# Layer_4.net
KiCad netlist of a schematic drawn in EAGLE
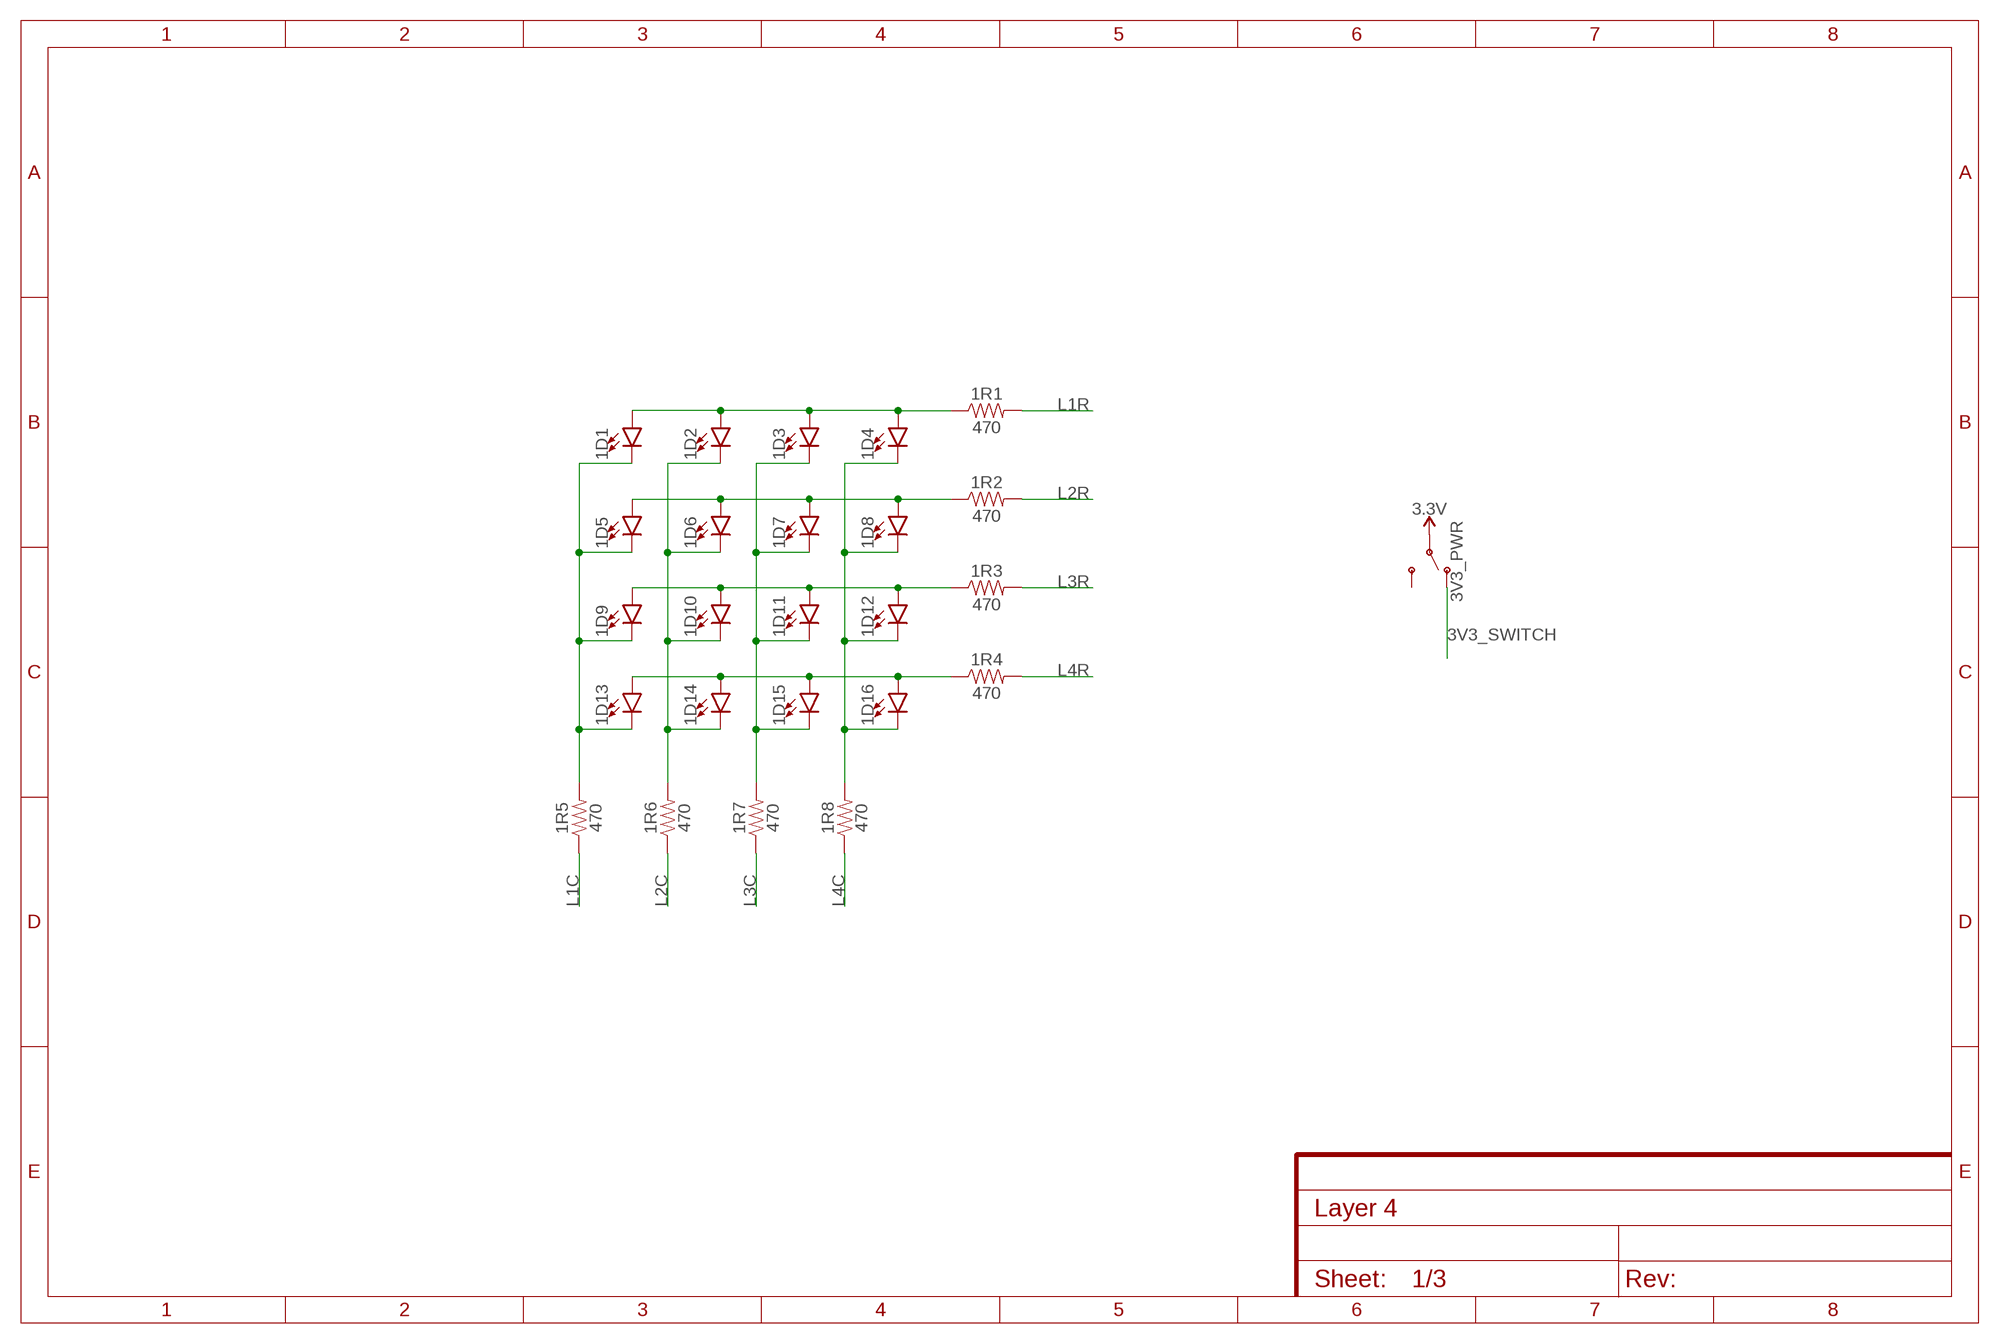
[diagram p0: schematic, sheet 1]
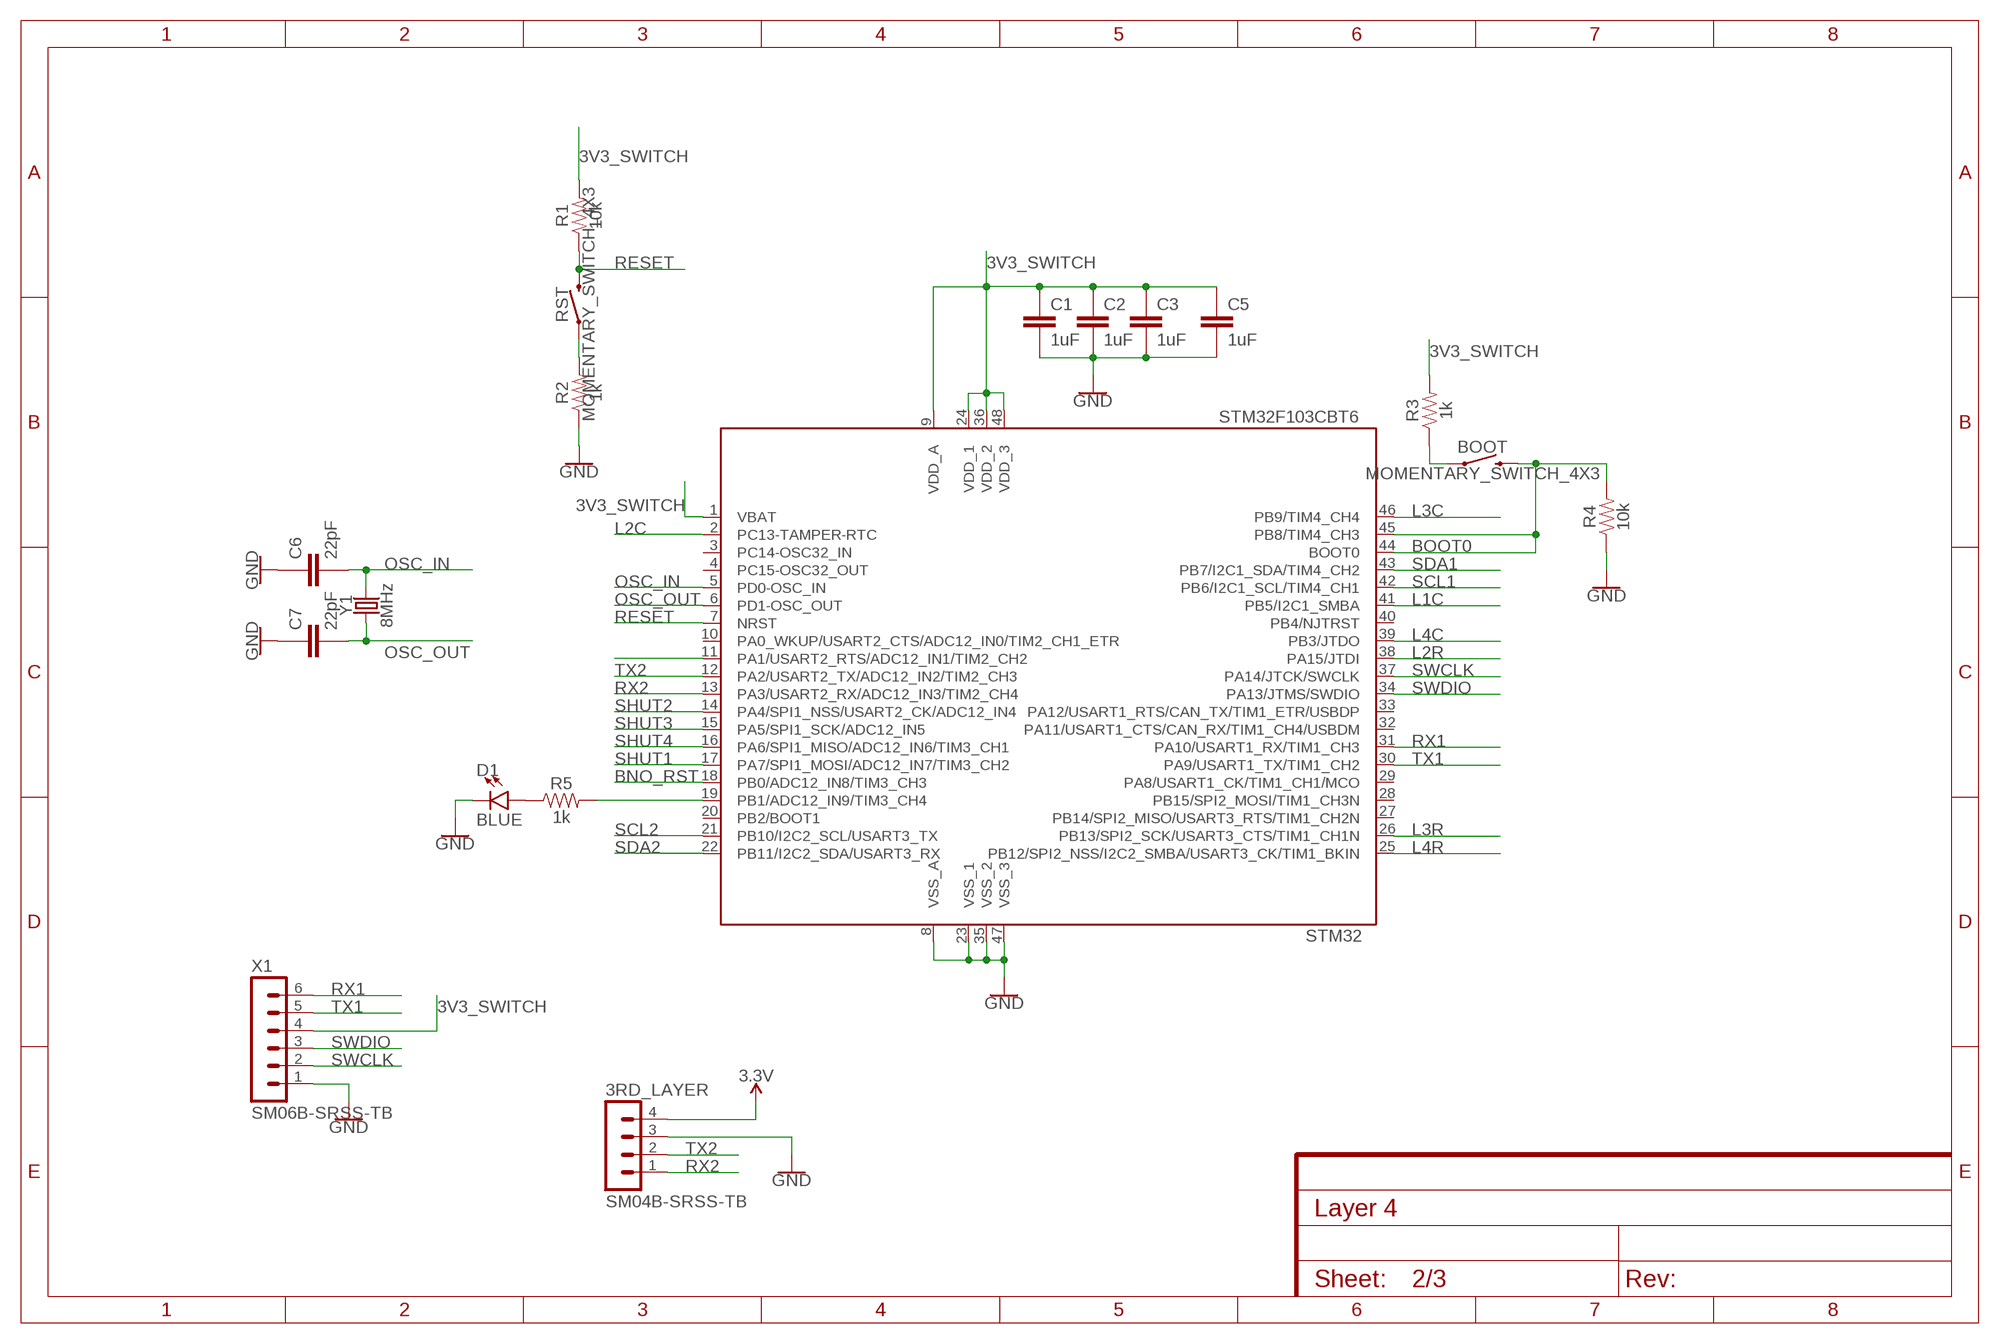
[diagram p1: schematic, sheet 2]
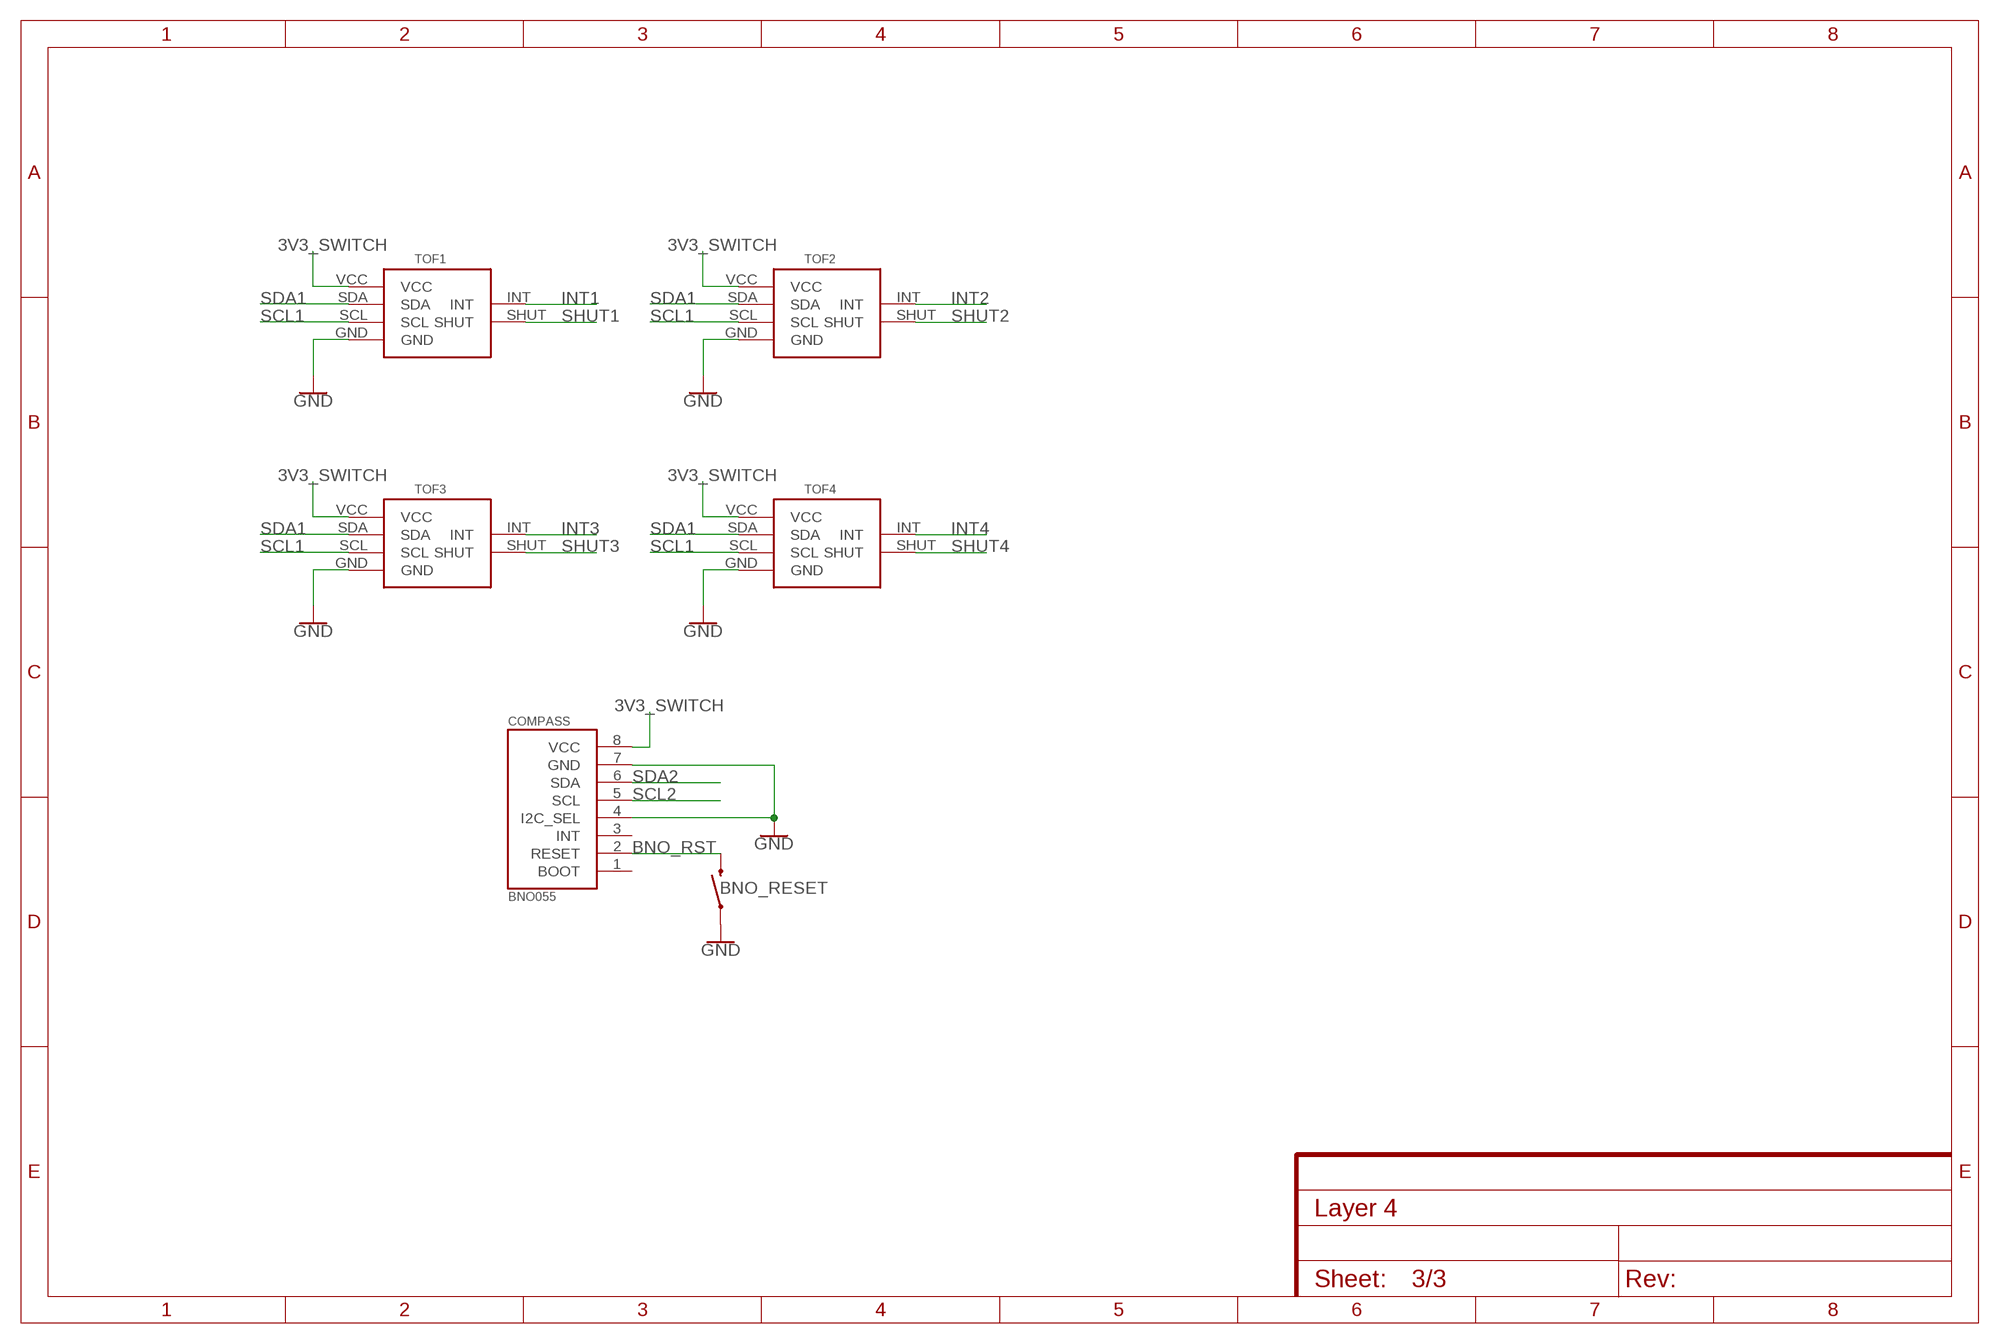
[diagram p2: schematic, sheet 3]

(export (version "E")
  (design (tool "Eeschema 10.0.6"))
  (components
    (comp (ref "1D1")
      (value "LED0603")
      (footprint "eagle-import:LED-0603")
      (libsource (lib "eagle-import") (part "LED0603"))
    )
    (comp (ref "1D2")
      (value "LED0603")
      (footprint "eagle-import:LED-0603")
      (libsource (lib "eagle-import") (part "LED0603"))
    )
    (comp (ref "1D3")
      (value "LED0603")
      (footprint "eagle-import:LED-0603")
      (libsource (lib "eagle-import") (part "LED0603"))
    )
    (comp (ref "1D4")
      (value "LED0603")
      (footprint "eagle-import:LED-0603")
      (libsource (lib "eagle-import") (part "LED0603"))
    )
    (comp (ref "1D5")
      (value "LED0603")
      (footprint "eagle-import:LED-0603")
      (libsource (lib "eagle-import") (part "LED0603"))
    )
    (comp (ref "1D6")
      (value "LED0603")
      (footprint "eagle-import:LED-0603")
      (libsource (lib "eagle-import") (part "LED0603"))
    )
    (comp (ref "1D7")
      (value "LED0603")
      (footprint "eagle-import:LED-0603")
      (libsource (lib "eagle-import") (part "LED0603"))
    )
    (comp (ref "1D8")
      (value "LED0603")
      (footprint "eagle-import:LED-0603")
      (libsource (lib "eagle-import") (part "LED0603"))
    )
    (comp (ref "1D9")
      (value "LED0603")
      (footprint "eagle-import:LED-0603")
      (libsource (lib "eagle-import") (part "LED0603"))
    )
    (comp (ref "1D10")
      (value "LED0603")
      (footprint "eagle-import:LED-0603")
      (libsource (lib "eagle-import") (part "LED0603"))
    )
    (comp (ref "1D11")
      (value "LED0603")
      (footprint "eagle-import:LED-0603")
      (libsource (lib "eagle-import") (part "LED0603"))
    )
    (comp (ref "1D12")
      (value "LED0603")
      (footprint "eagle-import:LED-0603")
      (libsource (lib "eagle-import") (part "LED0603"))
    )
    (comp (ref "1D13")
      (value "LED0603")
      (footprint "eagle-import:LED-0603")
      (libsource (lib "eagle-import") (part "LED0603"))
    )
    (comp (ref "1D14")
      (value "LED0603")
      (footprint "eagle-import:LED-0603")
      (libsource (lib "eagle-import") (part "LED0603"))
    )
    (comp (ref "1D15")
      (value "LED0603")
      (footprint "eagle-import:LED-0603")
      (libsource (lib "eagle-import") (part "LED0603"))
    )
    (comp (ref "1D16")
      (value "LED0603")
      (footprint "eagle-import:LED-0603")
      (libsource (lib "eagle-import") (part "LED0603"))
    )
    (comp (ref "1R1")
      (value "470")
      (footprint "eagle-import:R0603")
      (libsource (lib "eagle-import") (part "RESISTOR0603"))
    )
    (comp (ref "1R2")
      (value "470")
      (footprint "eagle-import:R0603")
      (libsource (lib "eagle-import") (part "RESISTOR0603"))
    )
    (comp (ref "1R3")
      (value "470")
      (footprint "eagle-import:R0603")
      (libsource (lib "eagle-import") (part "RESISTOR0603"))
    )
    (comp (ref "1R4")
      (value "470")
      (footprint "eagle-import:R0603")
      (libsource (lib "eagle-import") (part "RESISTOR0603"))
    )
    (comp (ref "1R5")
      (value "470")
      (footprint "eagle-import:R0603")
      (libsource (lib "eagle-import") (part "RESISTOR0603"))
    )
    (comp (ref "1R6")
      (value "470")
      (footprint "eagle-import:R0603")
      (libsource (lib "eagle-import") (part "RESISTOR0603"))
    )
    (comp (ref "1R7")
      (value "470")
      (footprint "eagle-import:R0603")
      (libsource (lib "eagle-import") (part "RESISTOR0603"))
    )
    (comp (ref "1R8")
      (value "470")
      (footprint "eagle-import:R0603")
      (libsource (lib "eagle-import") (part "RESISTOR0603"))
    )
    (comp (ref "3V3_PWR")
      (value "SWITCH-SPDT-PTH-11.6X4.0MM-LOCK")
      (footprint "eagle-import:SWITCH_SPDT_PTH_11.6X4.0MM_LOCK")
      (libsource (lib "eagle-import") (part "SWITCH-SPDT-PTH-11.6X4.0MM-LOCK"))
    )
    (comp (ref "3RD_LAYER")
      (value "SM04B-SRSS-TB")
      (footprint "eagle-import:SM04B-SRSS-TB")
      (libsource (lib "eagle-import") (part "SM04B-SRSS-TB"))
    )
    (comp (ref "BOOT")
      (value "MOMENTARY_SWITCH_4X3")
      (footprint "eagle-import:MOMENTARY_SWITCH_4X3")
      (libsource (lib "eagle-import") (part "MOMENTARY_SWITCH_4X3"))
    )
    (comp (ref "C1")
      (value "1uF")
      (footprint "eagle-import:C0603")
      (libsource (lib "eagle-import") (part "CAPACITOR0603"))
    )
    (comp (ref "C2")
      (value "1uF")
      (footprint "eagle-import:C0603")
      (libsource (lib "eagle-import") (part "CAPACITOR0603"))
    )
    (comp (ref "C3")
      (value "1uF")
      (footprint "eagle-import:C0603")
      (libsource (lib "eagle-import") (part "CAPACITOR0603"))
    )
    (comp (ref "C5")
      (value "1uF")
      (footprint "eagle-import:C0603")
      (libsource (lib "eagle-import") (part "CAPACITOR0603"))
    )
    (comp (ref "C6")
      (value "22pF")
      (footprint "eagle-import:C0603")
      (libsource (lib "eagle-import") (part "CAPACITOR0603"))
    )
    (comp (ref "C7")
      (value "22pF")
      (footprint "eagle-import:C0603")
      (libsource (lib "eagle-import") (part "CAPACITOR0603"))
    )
    (comp (ref "D1")
      (value "BLUE")
      (footprint "eagle-import:LED-0603")
      (libsource (lib "eagle-import") (part "LED0603"))
    )
    (comp (ref "R1")
      (value "10k")
      (footprint "eagle-import:R0603")
      (libsource (lib "eagle-import") (part "RESISTOR0603"))
    )
    (comp (ref "R2")
      (value "1k")
      (footprint "eagle-import:R0603")
      (libsource (lib "eagle-import") (part "RESISTOR0603"))
    )
    (comp (ref "R3")
      (value "1k")
      (footprint "eagle-import:R0603")
      (libsource (lib "eagle-import") (part "RESISTOR0603"))
    )
    (comp (ref "R4")
      (value "10k")
      (footprint "eagle-import:R0603")
      (libsource (lib "eagle-import") (part "RESISTOR0603"))
    )
    (comp (ref "R5")
      (value "1k")
      (footprint "eagle-import:R0603")
      (libsource (lib "eagle-import") (part "RESISTOR0603"))
    )
    (comp (ref "RST")
      (value "MOMENTARY_SWITCH_4X3")
      (footprint "eagle-import:MOMENTARY_SWITCH_4X3")
      (libsource (lib "eagle-import") (part "MOMENTARY_SWITCH_4X3"))
    )
    (comp (ref "STM32")
      (value "STM32F103CBT6")
      (footprint "eagle-import:LQFP48")
      (libsource (lib "eagle-import") (part "STM32F103CBT6"))
    )
    (comp (ref "X1")
      (value "SM06B-SRSS-TB")
      (footprint "eagle-import:SM06B-SRSS-TB")
      (libsource (lib "eagle-import") (part "SM06B-SRSS-TB"))
    )
    (comp (ref "Y1")
      (value "8MHz")
      (footprint "eagle-import:CRYSTAL-SMD-5X3.2-2PAD")
      (libsource (lib "eagle-import") (part "CRYSTALSMD-5X3.2-2PAD"))
    )
    (comp (ref "BNO_RESET")
      (value "MOMENTARY_SWITCH_4X3")
      (footprint "eagle-import:MOMENTARY_SWITCH_4X3")
      (libsource (lib "eagle-import") (part "MOMENTARY_SWITCH_4X3"))
    )
    (comp (ref "COMPASS")
      (value "BNO055")
      (footprint "eagle-import:BNO055")
      (libsource (lib "eagle-import") (part "BNO055"))
    )
    (comp (ref "TOF1")
      (value "VL53L1X")
      (footprint "eagle-import:VL53L1X_SLANTEDPINS")
      (libsource (lib "eagle-import") (part "VL53L1X"))
    )
    (comp (ref "TOF2")
      (value "VL53L1X")
      (footprint "eagle-import:VL53L1X_SLANTEDPINS")
      (libsource (lib "eagle-import") (part "VL53L1X"))
    )
    (comp (ref "TOF3")
      (value "VL53L1X")
      (footprint "eagle-import:VL53L1X_SLANTEDPINS")
      (libsource (lib "eagle-import") (part "VL53L1X"))
    )
    (comp (ref "TOF4")
      (value "VL53L1X")
      (footprint "eagle-import:VL53L1X_SLANTEDPINS")
      (libsource (lib "eagle-import") (part "VL53L1X"))
    )
  )
  (nets
    (net (code "1") (name "3.3V") (class "Default")
      (node (ref "3RD_LAYER") (pin "4") (pinfunction "4_4") (pintype "passive"))
      (node (ref "3V3_PWR") (pin "2") (pinfunction "P_2") (pintype "passive"))
    )
    (net (code "2") (name "3V3_SWITCH") (class "Default")
      (node (ref "3V3_PWR") (pin "1") (pinfunction "O_1") (pintype "passive"))
      (node (ref "C1") (pin "1") (pinfunction "1_1") (pintype "passive"))
      (node (ref "C2") (pin "1") (pinfunction "1_1") (pintype "passive"))
      (node (ref "C3") (pin "1") (pinfunction "1_1") (pintype "passive"))
      (node (ref "C5") (pin "2") (pinfunction "2_2") (pintype "passive"))
      (node (ref "COMPASS") (pin "8") (pinfunction "VCC_8") (pintype "bidirectional"))
      (node (ref "R1") (pin "2") (pinfunction "2_2") (pintype "passive"))
      (node (ref "R3") (pin "2") (pinfunction "2_2") (pintype "passive"))
      (node (ref "STM32") (pin "1") (pinfunction "VBAT_1") (pintype "power_in"))
      (node (ref "STM32") (pin "24") (pinfunction "VDD_1_24") (pintype "power_in"))
      (node (ref "STM32") (pin "36") (pinfunction "VDD_2_36") (pintype "power_in"))
      (node (ref "STM32") (pin "48") (pinfunction "VDD_3_48") (pintype "power_in"))
      (node (ref "STM32") (pin "9") (pinfunction "VDD_A_9") (pintype "power_in"))
      (node (ref "TOF1") (pin "VCC") (pinfunction "VCC_VCC") (pintype "power_in"))
      (node (ref "TOF2") (pin "VCC") (pinfunction "VCC_VCC") (pintype "power_in"))
      (node (ref "TOF3") (pin "VCC") (pinfunction "VCC_VCC") (pintype "power_in"))
      (node (ref "TOF4") (pin "VCC") (pinfunction "VCC_VCC") (pintype "power_in"))
      (node (ref "X1") (pin "4") (pinfunction "4_4") (pintype "passive"))
    )
    (net (code "3") (name "BNO_RST") (class "Default")
      (node (ref "BNO_RESET") (pin "P$2") (pinfunction "2_P$2") (pintype "passive"))
      (node (ref "COMPASS") (pin "2") (pinfunction "RESET_2") (pintype "bidirectional"))
      (node (ref "STM32") (pin "18") (pinfunction "PB0/ADC12_IN8/TIM3_CH3_18") (pintype "bidirectional"))
    )
    (net (code "4") (name "BOOT0") (class "Default")
      (node (ref "BOOT") (pin "P$2") (pinfunction "2_P$2") (pintype "passive"))
      (node (ref "R4") (pin "2") (pinfunction "2_2") (pintype "passive"))
      (node (ref "STM32") (pin "44") (pinfunction "BOOT0_44") (pintype "input"))
      (node (ref "STM32") (pin "45") (pinfunction "PB8/TIM4_CH3_45") (pintype "bidirectional"))
    )
    (net (code "5") (name "GND") (class "Default")
      (node (ref "3RD_LAYER") (pin "3") (pinfunction "3_3") (pintype "passive"))
      (node (ref "BNO_RESET") (pin "P$1") (pinfunction "1_P$1") (pintype "passive"))
      (node (ref "C1") (pin "2") (pinfunction "2_2") (pintype "passive"))
      (node (ref "C2") (pin "2") (pinfunction "2_2") (pintype "passive"))
      (node (ref "C3") (pin "2") (pinfunction "2_2") (pintype "passive"))
      (node (ref "C5") (pin "1") (pinfunction "1_1") (pintype "passive"))
      (node (ref "C6") (pin "1") (pinfunction "1_1") (pintype "passive"))
      (node (ref "C7") (pin "1") (pinfunction "1_1") (pintype "passive"))
      (node (ref "COMPASS") (pin "4") (pinfunction "I2C_SEL_4") (pintype "bidirectional"))
      (node (ref "COMPASS") (pin "7") (pinfunction "GND_7") (pintype "bidirectional"))
      (node (ref "D1") (pin "C") (pinfunction "C_C") (pintype "passive"))
      (node (ref "R2") (pin "1") (pinfunction "1_1") (pintype "passive"))
      (node (ref "R4") (pin "1") (pinfunction "1_1") (pintype "passive"))
      (node (ref "STM32") (pin "23") (pinfunction "VSS_1_23") (pintype "power_in"))
      (node (ref "STM32") (pin "35") (pinfunction "VSS_2_35") (pintype "power_in"))
      (node (ref "STM32") (pin "47") (pinfunction "VSS_3_47") (pintype "power_in"))
      (node (ref "STM32") (pin "8") (pinfunction "VSS_A_8") (pintype "power_in"))
      (node (ref "TOF1") (pin "GND") (pinfunction "GND_GND") (pintype "power_in"))
      (node (ref "TOF2") (pin "GND") (pinfunction "GND_GND") (pintype "power_in"))
      (node (ref "TOF3") (pin "GND") (pinfunction "GND_GND") (pintype "power_in"))
      (node (ref "TOF4") (pin "GND") (pinfunction "GND_GND") (pintype "power_in"))
      (node (ref "X1") (pin "1") (pinfunction "1_1") (pintype "passive"))
    )
    (net (code "6") (name "INT1") (class "Default")
      (node (ref "TOF1") (pin "INT") (pinfunction "INT_INT") (pintype "bidirectional"))
    )
    (net (code "7") (name "INT2") (class "Default")
      (node (ref "TOF2") (pin "INT") (pinfunction "INT_INT") (pintype "bidirectional"))
    )
    (net (code "8") (name "INT3") (class "Default")
      (node (ref "TOF3") (pin "INT") (pinfunction "INT_INT") (pintype "bidirectional"))
    )
    (net (code "9") (name "INT4") (class "Default")
      (node (ref "TOF4") (pin "INT") (pinfunction "INT_INT") (pintype "bidirectional"))
    )
    (net (code "10") (name "L1C") (class "Default")
      (node (ref "1R5") (pin "1") (pinfunction "1_1") (pintype "passive"))
      (node (ref "STM32") (pin "41") (pinfunction "PB5/I2C1_SMBA_41") (pintype "input"))
    )
    (net (code "11") (name "L1R") (class "Default")
      (node (ref "1R1") (pin "2") (pinfunction "2_2") (pintype "passive"))
      (node (ref "STM32") (pin "11") (pinfunction "PA1/USART2_RTS/ADC12_IN1/TIM2_CH2_11") (pintype "bidirectional"))
    )
    (net (code "12") (name "L2C") (class "Default")
      (node (ref "1R6") (pin "1") (pinfunction "1_1") (pintype "passive"))
      (node (ref "STM32") (pin "2") (pinfunction "PC13-TAMPER-RTC_2") (pintype "input"))
    )
    (net (code "13") (name "L2R") (class "Default")
      (node (ref "1R2") (pin "2") (pinfunction "2_2") (pintype "passive"))
      (node (ref "STM32") (pin "38") (pinfunction "PA15/JTDI_38") (pintype "bidirectional"))
    )
    (net (code "14") (name "L3C") (class "Default")
      (node (ref "1R7") (pin "1") (pinfunction "1_1") (pintype "passive"))
      (node (ref "STM32") (pin "46") (pinfunction "PB9/TIM4_CH4_46") (pintype "input"))
    )
    (net (code "15") (name "L3R") (class "Default")
      (node (ref "1R3") (pin "2") (pinfunction "2_2") (pintype "passive"))
      (node (ref "STM32") (pin "26") (pinfunction "PB13/SPI2_SCK/USART3_CTS/TIM1_CH1N_26") (pintype "input"))
    )
    (net (code "16") (name "L4C") (class "Default")
      (node (ref "1R8") (pin "1") (pinfunction "1_1") (pintype "passive"))
      (node (ref "STM32") (pin "39") (pinfunction "PB3/JTDO_39") (pintype "bidirectional"))
    )
    (net (code "17") (name "L4R") (class "Default")
      (node (ref "1R4") (pin "2") (pinfunction "2_2") (pintype "passive"))
      (node (ref "STM32") (pin "25") (pinfunction "PB12/SPI2_NSS/I2C2_SMBA/USART3_CK/TIM1_BKIN_25") (pintype "input"))
    )
    (net (code "18") (name "Net-(1D1-PadA)") (class "Default")
      (node (ref "1D1") (pin "A") (pinfunction "A_A") (pintype "passive"))
      (node (ref "1D2") (pin "A") (pinfunction "A_A") (pintype "passive"))
      (node (ref "1D3") (pin "A") (pinfunction "A_A") (pintype "passive"))
      (node (ref "1D4") (pin "A") (pinfunction "A_A") (pintype "passive"))
      (node (ref "1R1") (pin "1") (pinfunction "1_1") (pintype "passive"))
    )
    (net (code "19") (name "Net-(1D1-PadC)") (class "Default")
      (node (ref "1D1") (pin "C") (pinfunction "C_C") (pintype "passive"))
      (node (ref "1D13") (pin "C") (pinfunction "C_C") (pintype "passive"))
      (node (ref "1D5") (pin "C") (pinfunction "C_C") (pintype "passive"))
      (node (ref "1D9") (pin "C") (pinfunction "C_C") (pintype "passive"))
      (node (ref "1R5") (pin "2") (pinfunction "2_2") (pintype "passive"))
    )
    (net (code "20") (name "Net-(1D5-PadA)") (class "Default")
      (node (ref "1D5") (pin "A") (pinfunction "A_A") (pintype "passive"))
      (node (ref "1D6") (pin "A") (pinfunction "A_A") (pintype "passive"))
      (node (ref "1D7") (pin "A") (pinfunction "A_A") (pintype "passive"))
      (node (ref "1D8") (pin "A") (pinfunction "A_A") (pintype "passive"))
      (node (ref "1R2") (pin "1") (pinfunction "1_1") (pintype "passive"))
    )
    (net (code "21") (name "Net-(1D10-PadA)") (class "Default")
      (node (ref "1D10") (pin "A") (pinfunction "A_A") (pintype "passive"))
      (node (ref "1D11") (pin "A") (pinfunction "A_A") (pintype "passive"))
      (node (ref "1D12") (pin "A") (pinfunction "A_A") (pintype "passive"))
      (node (ref "1D9") (pin "A") (pinfunction "A_A") (pintype "passive"))
      (node (ref "1R3") (pin "1") (pinfunction "1_1") (pintype "passive"))
    )
    (net (code "22") (name "Net-(1D10-PadC)") (class "Default")
      (node (ref "1D10") (pin "C") (pinfunction "C_C") (pintype "passive"))
      (node (ref "1D14") (pin "C") (pinfunction "C_C") (pintype "passive"))
      (node (ref "1D2") (pin "C") (pinfunction "C_C") (pintype "passive"))
      (node (ref "1D6") (pin "C") (pinfunction "C_C") (pintype "passive"))
      (node (ref "1R6") (pin "2") (pinfunction "2_2") (pintype "passive"))
    )
    (net (code "23") (name "Net-(1D11-PadC)") (class "Default")
      (node (ref "1D11") (pin "C") (pinfunction "C_C") (pintype "passive"))
      (node (ref "1D15") (pin "C") (pinfunction "C_C") (pintype "passive"))
      (node (ref "1D3") (pin "C") (pinfunction "C_C") (pintype "passive"))
      (node (ref "1D7") (pin "C") (pinfunction "C_C") (pintype "passive"))
      (node (ref "1R7") (pin "2") (pinfunction "2_2") (pintype "passive"))
    )
    (net (code "24") (name "Net-(1D12-PadC)") (class "Default")
      (node (ref "1D12") (pin "C") (pinfunction "C_C") (pintype "passive"))
      (node (ref "1D16") (pin "C") (pinfunction "C_C") (pintype "passive"))
      (node (ref "1D4") (pin "C") (pinfunction "C_C") (pintype "passive"))
      (node (ref "1D8") (pin "C") (pinfunction "C_C") (pintype "passive"))
      (node (ref "1R8") (pin "2") (pinfunction "2_2") (pintype "passive"))
    )
    (net (code "25") (name "Net-(1D13-PadA)") (class "Default")
      (node (ref "1D13") (pin "A") (pinfunction "A_A") (pintype "passive"))
      (node (ref "1D14") (pin "A") (pinfunction "A_A") (pintype "passive"))
      (node (ref "1D15") (pin "A") (pinfunction "A_A") (pintype "passive"))
      (node (ref "1D16") (pin "A") (pinfunction "A_A") (pintype "passive"))
      (node (ref "1R4") (pin "1") (pinfunction "1_1") (pintype "passive"))
    )
    (net (code "26") (name "Net-(BOOT-1)") (class "Default")
      (node (ref "BOOT") (pin "P$1") (pinfunction "1_P$1") (pintype "passive"))
      (node (ref "R3") (pin "1") (pinfunction "1_1") (pintype "passive"))
    )
    (net (code "27") (name "Net-(D1-PadA)") (class "Default")
      (node (ref "D1") (pin "A") (pinfunction "A_A") (pintype "passive"))
      (node (ref "R5") (pin "1") (pinfunction "1_1") (pintype "passive"))
    )
    (net (code "28") (name "Net-(RST-1)") (class "Default")
      (node (ref "R2") (pin "2") (pinfunction "2_2") (pintype "passive"))
      (node (ref "RST") (pin "P$1") (pinfunction "1_P$1") (pintype "passive"))
    )
    (net (code "29") (name "Net-(STM32-PB1{slash}ADC12_IN9{slash}TIM3_CH4)") (class "Default")
      (node (ref "R5") (pin "2") (pinfunction "2_2") (pintype "passive"))
      (node (ref "STM32") (pin "19") (pinfunction "PB1/ADC12_IN9/TIM3_CH4_19") (pintype "bidirectional"))
    )
    (net (code "30") (name "OSC_IN") (class "Default")
      (node (ref "C6") (pin "2") (pinfunction "2_2") (pintype "passive"))
      (node (ref "STM32") (pin "5") (pinfunction "PD0-OSC_IN_5") (pintype "input"))
      (node (ref "Y1") (pin "P$2") (pinfunction "2_P$2") (pintype "passive"))
    )
    (net (code "31") (name "OSC_OUT") (class "Default")
      (node (ref "C7") (pin "2") (pinfunction "2_2") (pintype "passive"))
      (node (ref "STM32") (pin "6") (pinfunction "PD1-OSC_OUT_6") (pintype "input"))
      (node (ref "Y1") (pin "P$1") (pinfunction "1_P$1") (pintype "passive"))
    )
    (net (code "32") (name "RESET") (class "Default")
      (node (ref "R1") (pin "1") (pinfunction "1_1") (pintype "passive"))
      (node (ref "RST") (pin "P$2") (pinfunction "2_P$2") (pintype "passive"))
      (node (ref "STM32") (pin "7") (pinfunction "NRST_7") (pintype "input"))
    )
    (net (code "33") (name "RX1") (class "Default")
      (node (ref "STM32") (pin "31") (pinfunction "PA10/USART1_RX/TIM1_CH3_31") (pintype "bidirectional"))
      (node (ref "X1") (pin "6") (pinfunction "6_6") (pintype "passive"))
    )
    (net (code "34") (name "RX2") (class "Default")
      (node (ref "3RD_LAYER") (pin "1") (pinfunction "1_1") (pintype "passive"))
      (node (ref "STM32") (pin "13") (pinfunction "PA3/USART2_RX/ADC12_IN3/TIM2_CH4_13") (pintype "bidirectional"))
    )
    (net (code "35") (name "SCL1") (class "Default")
      (node (ref "STM32") (pin "42") (pinfunction "PB6/I2C1_SCL/TIM4_CH1_42") (pintype "input"))
      (node (ref "TOF1") (pin "SCL") (pinfunction "SCL_SCL") (pintype "bidirectional"))
      (node (ref "TOF2") (pin "SCL") (pinfunction "SCL_SCL") (pintype "bidirectional"))
      (node (ref "TOF3") (pin "SCL") (pinfunction "SCL_SCL") (pintype "bidirectional"))
      (node (ref "TOF4") (pin "SCL") (pinfunction "SCL_SCL") (pintype "bidirectional"))
    )
    (net (code "36") (name "SCL2") (class "Default")
      (node (ref "COMPASS") (pin "5") (pinfunction "SCL_5") (pintype "bidirectional"))
      (node (ref "STM32") (pin "21") (pinfunction "PB10/I2C2_SCL/USART3_TX_21") (pintype "input"))
    )
    (net (code "37") (name "SDA1") (class "Default")
      (node (ref "STM32") (pin "43") (pinfunction "PB7/I2C1_SDA/TIM4_CH2_43") (pintype "bidirectional"))
      (node (ref "TOF1") (pin "SDA") (pinfunction "SDA_SDA") (pintype "bidirectional"))
      (node (ref "TOF2") (pin "SDA") (pinfunction "SDA_SDA") (pintype "bidirectional"))
      (node (ref "TOF3") (pin "SDA") (pinfunction "SDA_SDA") (pintype "bidirectional"))
      (node (ref "TOF4") (pin "SDA") (pinfunction "SDA_SDA") (pintype "bidirectional"))
    )
    (net (code "38") (name "SDA2") (class "Default")
      (node (ref "COMPASS") (pin "6") (pinfunction "SDA_6") (pintype "bidirectional"))
      (node (ref "STM32") (pin "22") (pinfunction "PB11/I2C2_SDA/USART3_RX_22") (pintype "input"))
    )
    (net (code "39") (name "SHUT1") (class "Default")
      (node (ref "STM32") (pin "17") (pinfunction "PA7/SPI1_MOSI/ADC12_IN7/TIM3_CH2_17") (pintype "bidirectional"))
      (node (ref "TOF1") (pin "SHUT") (pinfunction "SHUT_SHUT") (pintype "bidirectional"))
    )
    (net (code "40") (name "SHUT2") (class "Default")
      (node (ref "STM32") (pin "14") (pinfunction "PA4/SPI1_NSS/USART2_CK/ADC12_IN4_14") (pintype "bidirectional"))
      (node (ref "TOF2") (pin "SHUT") (pinfunction "SHUT_SHUT") (pintype "bidirectional"))
    )
    (net (code "41") (name "SHUT3") (class "Default")
      (node (ref "STM32") (pin "15") (pinfunction "PA5/SPI1_SCK/ADC12_IN5_15") (pintype "bidirectional"))
      (node (ref "TOF3") (pin "SHUT") (pinfunction "SHUT_SHUT") (pintype "bidirectional"))
    )
    (net (code "42") (name "SHUT4") (class "Default")
      (node (ref "STM32") (pin "16") (pinfunction "PA6/SPI1_MISO/ADC12_IN6/TIM3_CH1_16") (pintype "bidirectional"))
      (node (ref "TOF4") (pin "SHUT") (pinfunction "SHUT_SHUT") (pintype "bidirectional"))
    )
    (net (code "43") (name "SWCLK") (class "Default")
      (node (ref "STM32") (pin "37") (pinfunction "PA14/JTCK/SWCLK_37") (pintype "bidirectional"))
      (node (ref "X1") (pin "2") (pinfunction "2_2") (pintype "passive"))
    )
    (net (code "44") (name "SWDIO") (class "Default")
      (node (ref "STM32") (pin "34") (pinfunction "PA13/JTMS/SWDIO_34") (pintype "bidirectional"))
      (node (ref "X1") (pin "3") (pinfunction "3_3") (pintype "passive"))
    )
    (net (code "45") (name "TX1") (class "Default")
      (node (ref "STM32") (pin "30") (pinfunction "PA9/USART1_TX/TIM1_CH2_30") (pintype "input"))
      (node (ref "X1") (pin "5") (pinfunction "5_5") (pintype "passive"))
    )
    (net (code "46") (name "TX2") (class "Default")
      (node (ref "3RD_LAYER") (pin "2") (pinfunction "2_2") (pintype "passive"))
      (node (ref "STM32") (pin "12") (pinfunction "PA2/USART2_TX/ADC12_IN2/TIM2_CH3_12") (pintype "bidirectional"))
    )
    (net (code "47") (name "unconnected-(3V3_PWR-S-Pad3)") (class "Default")
      (node (ref "3V3_PWR") (pin "3") (pinfunction "S_3") (pintype "passive"))
    )
    (net (code "48") (name "unconnected-(COMPASS-BOOT-Pad1)") (class "Default")
      (node (ref "COMPASS") (pin "1") (pinfunction "BOOT_1") (pintype "bidirectional"))
    )
    (net (code "49") (name "unconnected-(COMPASS-INT-Pad3)") (class "Default")
      (node (ref "COMPASS") (pin "3") (pinfunction "INT_3") (pintype "bidirectional"))
    )
    (net (code "50") (name "unconnected-(STM32-PA0_WKUP{slash}USART2_CTS{slash}ADC12_IN0{slash}TIM2_CH1_ETR-Pad10)") (class "Default")
      (node (ref "STM32") (pin "10") (pinfunction "PA0_WKUP/USART2_CTS/ADC12_IN0/TIM2_CH1_ETR_10") (pintype "bidirectional"))
    )
    (net (code "51") (name "unconnected-(STM32-PA8{slash}USART1_CK{slash}TIM1_CH1{slash}MCO-Pad29)") (class "Default")
      (node (ref "STM32") (pin "29") (pinfunction "PA8/USART1_CK/TIM1_CH1/MCO_29") (pintype "bidirectional"))
    )
    (net (code "52") (name "unconnected-(STM32-PA11{slash}USART1_CTS{slash}CAN_RX{slash}TIM1_CH4{slash}USBDM-Pad32)") (class "Default")
      (node (ref "STM32") (pin "32") (pinfunction "PA11/USART1_CTS/CAN_RX/TIM1_CH4/USBDM_32") (pintype "bidirectional"))
    )
    (net (code "53") (name "unconnected-(STM32-PA12{slash}USART1_RTS{slash}CAN_TX{slash}TIM1_ETR{slash}USBDP-Pad33)") (class "Default")
      (node (ref "STM32") (pin "33") (pinfunction "PA12/USART1_RTS/CAN_TX/TIM1_ETR/USBDP_33") (pintype "bidirectional"))
    )
    (net (code "54") (name "unconnected-(STM32-PB2{slash}BOOT1-Pad20)") (class "Default")
      (node (ref "STM32") (pin "20") (pinfunction "PB2/BOOT1_20") (pintype "bidirectional"))
    )
    (net (code "55") (name "unconnected-(STM32-PB4{slash}NJTRST-Pad40)") (class "Default")
      (node (ref "STM32") (pin "40") (pinfunction "PB4/NJTRST_40") (pintype "bidirectional"))
    )
    (net (code "56") (name "unconnected-(STM32-PB14{slash}SPI2_MISO{slash}USART3_RTS{slash}TIM1_CH2N-Pad27)") (class "Default")
      (node (ref "STM32") (pin "27") (pinfunction "PB14/SPI2_MISO/USART3_RTS/TIM1_CH2N_27") (pintype "input"))
    )
    (net (code "57") (name "unconnected-(STM32-PB15{slash}SPI2_MOSI{slash}TIM1_CH3N-Pad28)") (class "Default")
      (node (ref "STM32") (pin "28") (pinfunction "PB15/SPI2_MOSI/TIM1_CH3N_28") (pintype "input"))
    )
    (net (code "58") (name "unconnected-(STM32-PC14-OSC32_IN-Pad3)") (class "Default")
      (node (ref "STM32") (pin "3") (pinfunction "PC14-OSC32_IN_3") (pintype "input"))
    )
    (net (code "59") (name "unconnected-(STM32-PC15-OSC32_OUT-Pad4)") (class "Default")
      (node (ref "STM32") (pin "4") (pinfunction "PC15-OSC32_OUT_4") (pintype "input"))
    )
  )
)
